# 5_SurvBot_RCU_Sensors.net
KiCad netlist of a schematic drawn in Altium Designer
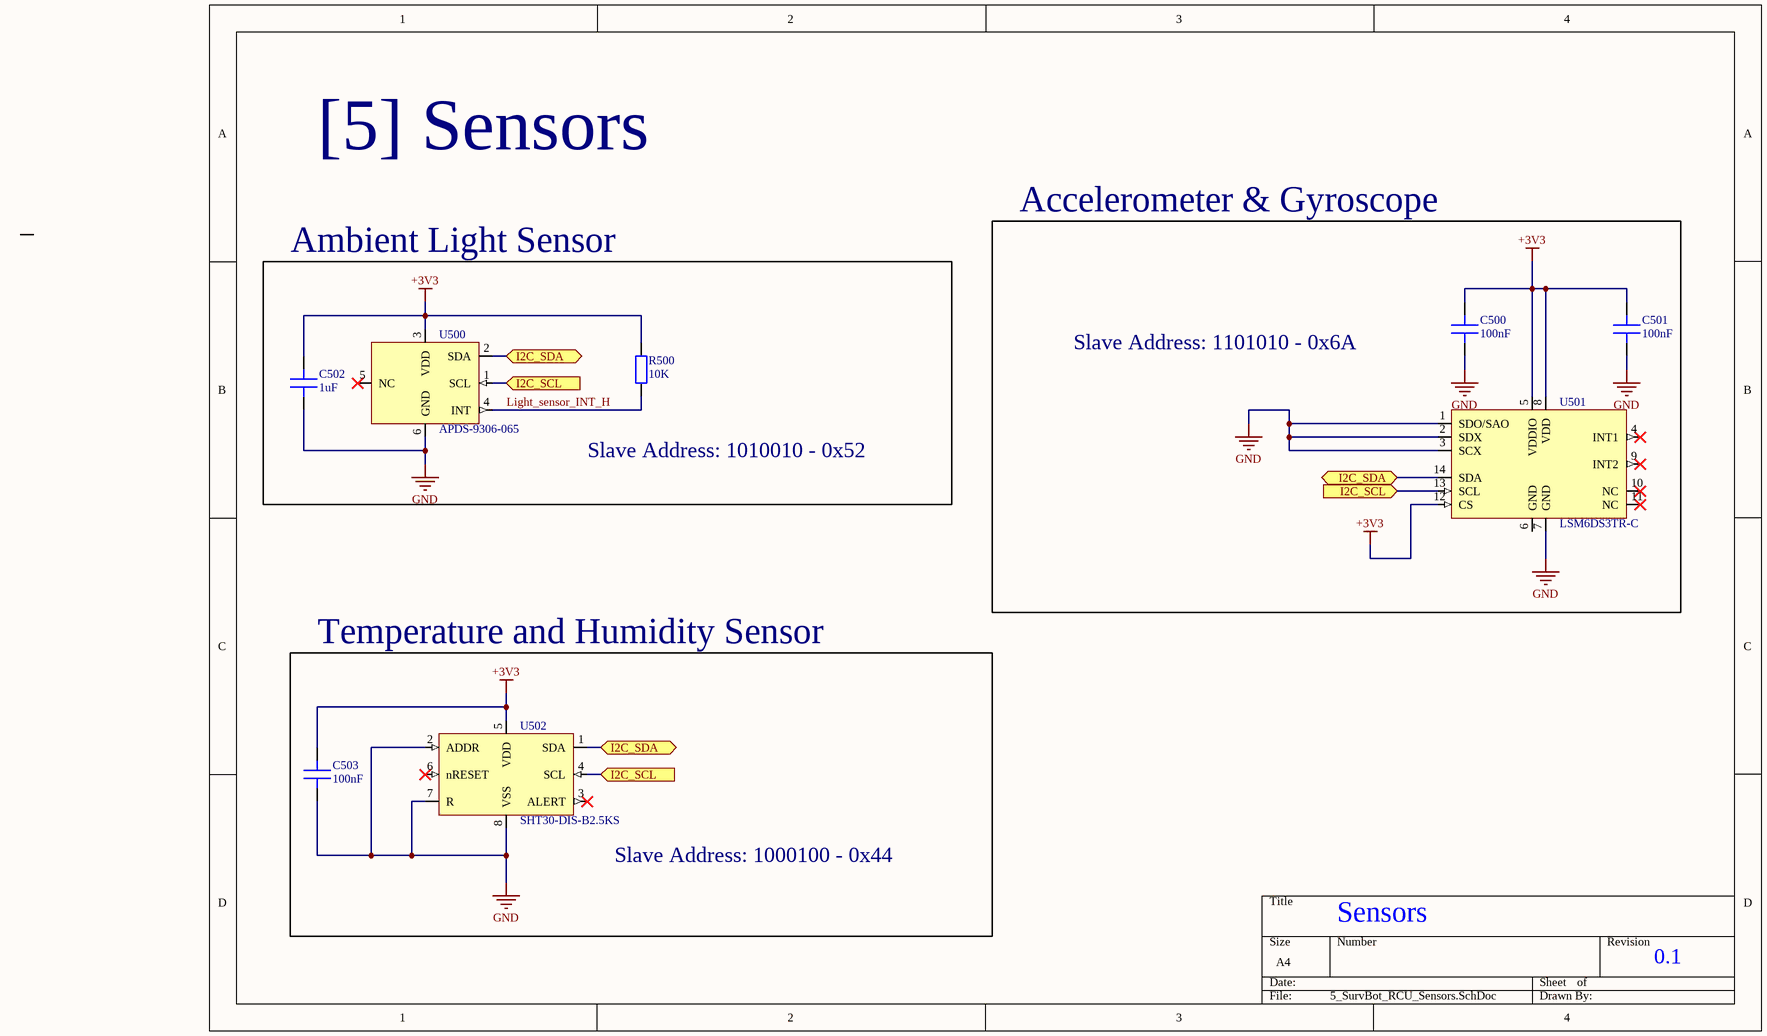
[diagram p0: 5_SurvBot_RCU_Sensors.SchDoc]

(export (version "E")
  (design (tool "Eeschema 10.0.6"))
  (components
    (comp (ref "C500")
      (value "100nF")
      (footprint "CAP_0603")
      (description "0.1 µF ±10% 50V Ceramic Capacitor X7R 0603 (1608 Metric)")
      (fields (field (name "MANUFACTURER") "KEMET") (field (name "MANUFACTURER PART #") "C0603C104K5RACAUTO"))
      (libsource (lib "GhaniLibrary") (part "CAP_100nF-50V-10%-0603"))
    )
    (comp (ref "C501")
      (value "100nF")
      (footprint "CAP_0603")
      (description "0.1 µF ±10% 50V Ceramic Capacitor X7R 0603 (1608 Metric)")
      (fields (field (name "MANUFACTURER") "KEMET") (field (name "MANUFACTURER PART #") "C0603C104K5RACAUTO"))
      (libsource (lib "GhaniLibrary") (part "CAP_100nF-50V-10%-0603"))
    )
    (comp (ref "C502")
      (value "1uF")
      (footprint "CAP_0603")
      (description "1 µF ±10% 16V Ceramic Capacitor X7R 0603 (1608 Metric)")
      (fields (field (name "MANUFACTURER") "YAGEO") (field (name "MANUFACTURER PART #") "CC0603KRX7R7BB105"))
      (libsource (lib "GhaniLibrary") (part "CAP_1uF-16V-10%-0603"))
    )
    (comp (ref "C503")
      (value "100nF")
      (footprint "CAP_0603")
      (description "0.1 µF ±10% 50V Ceramic Capacitor X7R 0603 (1608 Metric)")
      (fields (field (name "MANUFACTURER") "KEMET") (field (name "MANUFACTURER PART #") "C0603C104K5RACAUTO"))
      (libsource (lib "GhaniLibrary") (part "CAP_100nF-50V-10%-0603"))
    )
    (comp (ref "R500")
      (value "10K")
      (footprint "RES_0603")
      (description "10 kOhms ±1% 0.1W, 1/10W Chip Resistor 0603 (1608 Metric) Moisture Resistant Thick Film")
      (fields (field (name "MANUFACTURER") "YAGEO") (field (name "MANUFACTURER PART #") "RC0603FR-0710KL"))
      (libsource (lib "GhaniLibrary") (part "RES_10K-100mW-1%-0603"))
    )
    (comp (ref "U500")
      (value "APDS-9306-065")
      (footprint "APDS-9306-065")
      (description "Optical Sensor Ambient 560nm I2C 6-SMD Module")
      (fields (field (name "MANUFACTURER") "Broadcom/AVAGO"))
      (libsource (lib "GhaniLibrary") (part "IC_APDS-9306-065"))
    )
    (comp (ref "U501")
      (value "LSM6DS3TR-C")
      (footprint "LGA-14_LSM6DS3TR-C")
      (description "Accelerometer, Gyroscope, Temperature, 6 Axis Sensor I2C, SPI Output")
      (fields (field (name "MANUFACTURER") "STMicroelectronics"))
      (libsource (lib "GhaniLibrary") (part "IC_LSM6DS3TR-C"))
    )
    (comp (ref "U502")
      (value "SHT30-DIS-B2.5KS")
      (footprint "8-VFDFN Exposed Pad")
      (description "Humidity, Temperature 0 ~ 100% RH I2C ±2% RH 8 s Surface Mount")
      (fields (field (name "MANUFACTURER") "Sensirion"))
      (libsource (lib "GhaniLibrary") (part "IC_SHT30-DIS-B2.5KS"))
    )
  )
  (nets
    (net (code "1") (name "+3V3") (class "Default")
      (node (ref "C500") (pin "2") (pinfunction "0_2") (pintype "passive"))
      (node (ref "C501") (pin "2") (pinfunction "0_2") (pintype "passive"))
      (node (ref "C502") (pin "2") (pinfunction "0_2") (pintype "passive"))
      (node (ref "C503") (pin "2") (pinfunction "0_2") (pintype "passive"))
      (node (ref "R500") (pin "2") (pinfunction "2_2") (pintype "passive"))
      (node (ref "U500") (pin "3") (pinfunction "VDD_3") (pintype "power_in"))
      (node (ref "U501") (pin "12") (pinfunction "CS_12") (pintype "input"))
      (node (ref "U501") (pin "5") (pinfunction "VDDIO_5") (pintype "power_in"))
      (node (ref "U501") (pin "8") (pinfunction "VDD_8") (pintype "power_in"))
      (node (ref "U502") (pin "5") (pinfunction "VDD_5") (pintype "power_in"))
    )
    (net (code "2") (name "/I2C_SCL") (class "Default")
      (node (ref "U500") (pin "1") (pinfunction "SCL_1") (pintype "input"))
      (node (ref "U501") (pin "13") (pinfunction "SCL_13") (pintype "input"))
      (node (ref "U502") (pin "4") (pinfunction "SCL_4") (pintype "input"))
    )
    (net (code "3") (name "/I2C_SDA") (class "Default")
      (node (ref "U500") (pin "2") (pinfunction "SDA_2") (pintype "bidirectional"))
      (node (ref "U501") (pin "14") (pinfunction "SDA_14") (pintype "bidirectional"))
      (node (ref "U502") (pin "1") (pinfunction "SDA_1") (pintype "bidirectional"))
    )
    (net (code "4") (name "/Light_sensor_INT_H") (class "Default")
      (node (ref "R500") (pin "1") (pinfunction "1_1") (pintype "passive"))
      (node (ref "U500") (pin "4") (pinfunction "INT_4") (pintype "output"))
    )
    (net (code "5") (name "GND") (class "Default")
      (node (ref "C500") (pin "1") (pinfunction "0_1") (pintype "passive"))
      (node (ref "C501") (pin "1") (pinfunction "0_1") (pintype "passive"))
      (node (ref "C502") (pin "1") (pinfunction "0_1") (pintype "passive"))
      (node (ref "C503") (pin "1") (pinfunction "0_1") (pintype "passive"))
      (node (ref "U500") (pin "6") (pinfunction "GND_6") (pintype "power_in"))
      (node (ref "U501") (pin "1") (pinfunction "SDO/SAO_1") (pintype "bidirectional"))
      (node (ref "U501") (pin "2") (pinfunction "SDX_2") (pintype "bidirectional"))
      (node (ref "U501") (pin "3") (pinfunction "SCX_3") (pintype "bidirectional"))
      (node (ref "U501") (pin "7") (pinfunction "GND_7") (pintype "power_in"))
      (node (ref "U502") (pin "2") (pinfunction "ADDR_2") (pintype "input"))
      (node (ref "U502") (pin "7") (pinfunction "R_7") (pintype "passive"))
      (node (ref "U502") (pin "8") (pinfunction "VSS_8") (pintype "power_in"))
    )
    (net (code "6") (name "unconnected-(U500-NC-Pad5)") (class "Default")
      (node (ref "U500") (pin "5") (pinfunction "NC_5") (pintype "passive+no_connect"))
    )
    (net (code "7") (name "unconnected-(U501-GND-Pad6)") (class "Default")
      (node (ref "U501") (pin "6") (pinfunction "GND_6") (pintype "power_in"))
    )
    (net (code "8") (name "unconnected-(U501-INT1-Pad4)") (class "Default")
      (node (ref "U501") (pin "4") (pinfunction "INT1_4") (pintype "output+no_connect"))
    )
    (net (code "9") (name "unconnected-(U501-INT2-Pad9)") (class "Default")
      (node (ref "U501") (pin "9") (pinfunction "INT2_9") (pintype "output+no_connect"))
    )
    (net (code "10") (name "unconnected-(U501-NC-Pad10)") (class "Default")
      (node (ref "U501") (pin "10") (pinfunction "NC_10") (pintype "passive+no_connect"))
    )
    (net (code "11") (name "unconnected-(U501-NC-Pad11)") (class "Default")
      (node (ref "U501") (pin "11") (pinfunction "NC_11") (pintype "passive+no_connect"))
    )
    (net (code "12") (name "unconnected-(U502-ALERT-Pad3)") (class "Default")
      (node (ref "U502") (pin "3") (pinfunction "ALERT_3") (pintype "output+no_connect"))
    )
    (net (code "13") (name "unconnected-(U502-nRESET-Pad6)") (class "Default")
      (node (ref "U502") (pin "6") (pinfunction "nRESET_6") (pintype "input+no_connect"))
    )
  )
)
